# PR2387_FETs.net
KiCad netlist of a schematic drawn in Altium Designer
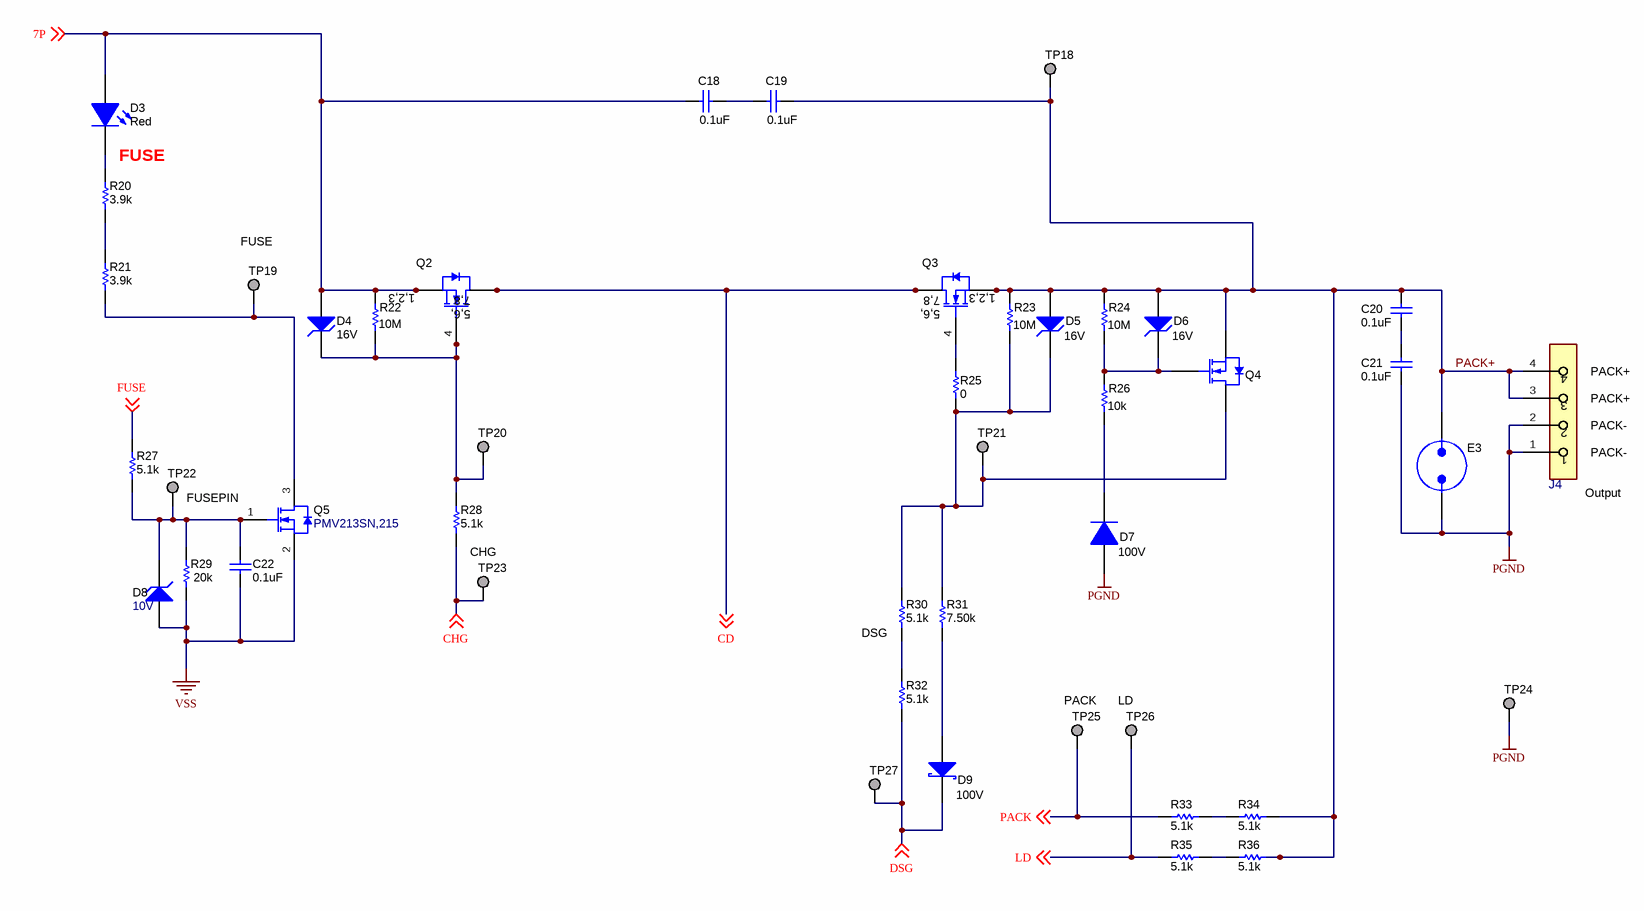
[diagram p0: PR2387_FETs.SchDoc]

(export (version "E")
  (design (tool "Eeschema 10.0.6"))
  (components
    (comp (ref "C18")
      (value "GCJ188R72A104KA01D")
      (footprint "0603")
      (description "CAP, CERM, 0.1 uF, 100 V,+/- 10%, X7R, AEC-Q200 Grade 1, 0603")
      (fields
        (field (name "MANUFACTURER") "MuRata")
        (field (name "VALUEDISPLAYED") "0.1uF")
        (field (name "PUBLISHER") "Texas Instruments")
      )
      (libsource (lib "Altium Vault - TI") (part "Capacitor"))
    )
    (comp (ref "C19")
      (value "GCJ188R72A104KA01D")
      (footprint "0603")
      (description "CAP, CERM, 0.1 uF, 100 V,+/- 10%, X7R, AEC-Q200 Grade 1, 0603")
      (fields
        (field (name "MANUFACTURER") "MuRata")
        (field (name "VALUEDISPLAYED") "0.1uF")
        (field (name "PUBLISHER") "Texas Instruments")
      )
      (libsource (lib "Altium Vault - TI") (part "Capacitor"))
    )
    (comp (ref "C20")
      (value "GCJ188R72A104KA01D")
      (footprint "0603")
      (description "CAP, CERM, 0.1 uF, 100 V,+/- 10%, X7R, AEC-Q200 Grade 1, 0603")
      (fields
        (field (name "MANUFACTURER") "MuRata")
        (field (name "VALUEDISPLAYED") "0.1uF")
        (field (name "PUBLISHER") "Texas Instruments")
      )
      (libsource (lib "Altium Vault - TI") (part "Capacitor"))
    )
    (comp (ref "C21")
      (value "GCJ188R72A104KA01D")
      (footprint "0603")
      (description "CAP, CERM, 0.1 uF, 100 V,+/- 10%, X7R, AEC-Q200 Grade 1, 0603")
      (fields
        (field (name "MANUFACTURER") "MuRata")
        (field (name "VALUEDISPLAYED") "0.1uF")
        (field (name "PUBLISHER") "Texas Instruments")
      )
      (libsource (lib "Altium Vault - TI") (part "Capacitor"))
    )
    (comp (ref "C22")
      (value "885012206095")
      (footprint "0603")
      (description "CAP, CERM, 0.1 uF, 50 V, +/- 10%, X7R, 0603")
      (fields
        (field (name "VALUEDISPLAYED") "0.1uF")
        (field (name "MANUFACTURER") "Wurth Elektronik")
        (field (name "PUBLISHER") "Texas Instruments")
      )
      (libsource (lib "Altium Vault - TI") (part "Capacitor"))
    )
    (comp (ref "D3")
      (value "Red")
      (footprint "WL-SMCW_RED")
      (description "LED, Red, SMD")
      (fields (field (name "MANUFACTURER") "Wurth Elektronik") (field (name "PARTNUMBER") "150060RS75000"))
      (libsource (lib "Altium Vault - TI") (part "CMP-0002947-3"))
    )
    (comp (ref "D4")
      (value "16V")
      (footprint "SOD-123")
      (description "Diode, Zener, 16 V, 500 mW, SOD-123")
      (fields (field (name "MANUFACTURER") "Diodes Inc.") (field (name "PARTNUMBER") "MMSZ5246B-7-F"))
      (libsource (lib "Altium Vault - TI") (part "Zener"))
    )
    (comp (ref "D5")
      (value "16V")
      (footprint "SOD-123")
      (description "Diode, Zener, 16 V, 500 mW, SOD-123")
      (fields (field (name "PARTNUMBER") "MMSZ5246B-7-F") (field (name "MANUFACTURER") "Diodes Inc."))
      (libsource (lib "Altium Vault - TI") (part "CMP-0005754-4"))
    )
    (comp (ref "D6")
      (value "16V")
      (footprint "SOD-123")
      (description "Diode, Zener, 16 V, 500 mW, SOD-123")
      (fields (field (name "PARTNUMBER") "MMSZ5246B-7-F") (field (name "MANUFACTURER") "Diodes Inc."))
      (libsource (lib "Altium Vault - TI") (part "CMP-0005754-4"))
    )
    (comp (ref "D7")
      (value "100V")
      (footprint "SOD-123")
      (description "Diode, Ultrafast, 100 V, 0.15 A, SOD-123")
      (fields (field (name "PARTNUMBER") "1N4148W-7-F") (field (name "MANUFACTURER") "Diodes Inc."))
      (libsource (lib "Altium Vault - TI") (part "CMP-0029001-2"))
    )
    (comp (ref "D8")
      (value "10V")
      (footprint "SOD-123")
      (description "Diode, Zener, 10 V, 500 mW, SOD-123")
      (fields (field (name "MANUFACTURER") "ON Semiconductor") (field (name "PARTNUMBER") "MMSZ4697T1G"))
      (libsource (lib "Altium Vault - TI") (part "Zener"))
    )
    (comp (ref "D9")
      (value "BAT46W-7-F")
      (footprint "SOD-123")
      (description "Diode, Schottky, 100 V, 0.15 A, SOD-123")
      (fields (field (name "MANUFACTURER") "Diodes Inc.") (field (name "VR_V") "100V"))
      (libsource (lib "Altium Vault - TI") (part "DIODE_SCHOTTKY"))
    )
    (comp (ref "E3")
      (value "Spark Gap")
      (footprint "SPARK_GAP2")
      (libsource (lib "Altium Vault - TI") (part "CMP-0079939-1"))
    )
    (comp (ref "J4")
      (value "OSTTE040161")
      (footprint "FP-OSTTE040161_HDR4-MFG")
      (description "TERM BLOCK 3.5MM VERT 4POS PCB")
      (fields (field (name "MANUFACTURER") "On Shore Technology"))
      (libsource (lib "Altium Vault - TI") (part "SYM-OSTTE040161"))
    )
    (comp (ref "Q2")
      (value "CSD19532Q5B")
      (footprint "DNK0008A")
      (description "MOSFET, N-CH, 100 V, 17 A, DNK0008A (VSON-CLIP-8)")
      (fields (field (name "MANUFACTURER") "Texas Instruments"))
      (libsource (lib "Altium Vault - TI") (part "MOSFET_N_D56789G4S123"))
    )
    (comp (ref "Q3")
      (value "CSD19532Q5B")
      (footprint "DNK0008A")
      (description "MOSFET, N-CH, 100 V, 17 A, DNK0008A (VSON-CLIP-8)")
      (fields (field (name "MANUFACTURER") "Texas Instruments"))
      (libsource (lib "Altium Vault - TI") (part "MOSFET_N_D56789G4S123"))
    )
    (comp (ref "Q4")
      (value "MOSFET_N_D3G1S2")
      (footprint "SOT-323")
      (description "MOSFET, N-CH, 60 V, 0.31 A, SOT-323")
      (fields
        (field (name "PARTNUMBER") "2N7002KW")
        (field (name "MANUFACTURER") "Fairchild Semiconductor")
        (field (name "PUBLISHER") "Texas Instruments")
      )
      (libsource (lib "Altium Vault - TI") (part "CMP-0000774-1"))
    )
    (comp (ref "Q5")
      (value "PMV213SN,215")
      (footprint "SOT-23")
      (description "MOSFET, N-CH, 100 V, 1.9 A, SOT-23")
      (fields (field (name "MANUFACTURER") "Nexperia"))
      (libsource (lib "Altium Vault - TI") (part "MOSFET_N_D3G1S2"))
    )
    (comp (ref "R20")
      (value "CRCW06033K90JNEA")
      (footprint "0603")
      (description "RES, 3.9 k, 5%, 0.1 W, AEC-Q200 Grade 0, 0603")
      (fields (field (name "MANUFACTURER") "Vishay-Dale") (field (name "VALUEDISPLAYED") "3.9k"))
      (libsource (lib "Altium Vault - TI") (part "Resistor"))
    )
    (comp (ref "R21")
      (value "CRCW06033K90JNEA")
      (footprint "0603")
      (description "RES, 3.9 k, 5%, 0.1 W, AEC-Q200 Grade 0, 0603")
      (fields (field (name "MANUFACTURER") "Vishay-Dale") (field (name "VALUEDISPLAYED") "3.9k"))
      (libsource (lib "Altium Vault - TI") (part "Resistor"))
    )
    (comp (ref "R22")
      (value "Resistor")
      (footprint "0603")
      (description "RES, 10 M, 5%, 0.1 W, AEC-Q200 Grade 0, 0603")
      (fields
        (field (name "PARTNUMBER") "CRCW060310M0JNEA")
        (field (name "MANUFACTURER") "Vishay-Dale")
        (field (name "VALUEDISPLAYED") "10M")
        (field (name "PUBLISHER") "Texas Instruments")
      )
      (libsource (lib "Altium Vault - TI") (part "Resistor"))
    )
    (comp (ref "R23")
      (value "Resistor")
      (footprint "0603")
      (description "RES, 10 M, 5%, 0.1 W, AEC-Q200 Grade 0, 0603")
      (fields
        (field (name "PARTNUMBER") "CRCW060310M0JNEA")
        (field (name "MANUFACTURER") "Vishay-Dale")
        (field (name "VALUEDISPLAYED") "10M")
        (field (name "PUBLISHER") "Texas Instruments")
      )
      (libsource (lib "Altium Vault - TI") (part "Resistor"))
    )
    (comp (ref "R24")
      (value "Resistor")
      (footprint "0603")
      (description "RES, 10 M, 5%, 0.1 W, AEC-Q200 Grade 0, 0603")
      (fields
        (field (name "PARTNUMBER") "CRCW060310M0JNEA")
        (field (name "MANUFACTURER") "Vishay-Dale")
        (field (name "VALUEDISPLAYED") "10M")
        (field (name "PUBLISHER") "Texas Instruments")
      )
      (libsource (lib "Altium Vault - TI") (part "Resistor"))
    )
    (comp (ref "R25")
      (value "CRCW06030000Z0EA")
      (footprint "0603")
      (description "RES, 0, 5%, 0.1 W, AEC-Q200 Grade 0, 0603")
      (fields (field (name "MANUFACTURER") "Vishay-Dale") (field (name "VALUEDISPLAYED") "0"))
      (libsource (lib "Altium Vault - TI") (part "Resistor"))
    )
    (comp (ref "R26")
      (value "Resistor")
      (footprint "0603")
      (description "RES, 10 k, 5%, 0.1 W, AEC-Q200 Grade 0, 0603")
      (fields
        (field (name "PARTNUMBER") "CRCW060310K0JNEA")
        (field (name "MANUFACTURER") "Vishay-Dale")
        (field (name "VALUEDISPLAYED") "10k")
        (field (name "PUBLISHER") "Texas Instruments")
      )
      (libsource (lib "Altium Vault - TI") (part "Resistor"))
    )
    (comp (ref "R27")
      (value "Resistor")
      (footprint "0603")
      (description "RES, 5.1 k, 5%, 0.1 W, AEC-Q200 Grade 0, 0603")
      (fields
        (field (name "PARTNUMBER") "CRCW06035K10JNEA")
        (field (name "MANUFACTURER") "Vishay-Dale")
        (field (name "VALUEDISPLAYED") "5.1k")
        (field (name "PUBLISHER") "Texas Instruments")
      )
      (libsource (lib "Altium Vault - TI") (part "Resistor"))
    )
    (comp (ref "R28")
      (value "CRCW06035K10JNEA")
      (footprint "0603")
      (description "RES, 5.1 k, 5%, 0.1 W, AEC-Q200 Grade 0, 0603")
      (fields (field (name "VALUEDISPLAYED") "5.1k") (field (name "MANUFACTURER") "Vishay-Dale"))
      (libsource (lib "Altium Vault - TI") (part "Resistor"))
    )
    (comp (ref "R29")
      (value "Resistor")
      (footprint "0603")
      (description "RES, 20 k, 5%, 0.1 W, AEC-Q200 Grade 0, 0603")
      (fields
        (field (name "PARTNUMBER") "CRCW060320K0JNEA")
        (field (name "MANUFACTURER") "Vishay-Dale")
        (field (name "VALUEDISPLAYED") "20k")
        (field (name "PUBLISHER") "Texas Instruments")
      )
      (libsource (lib "Altium Vault - TI") (part "Resistor"))
    )
    (comp (ref "R30")
      (value "CRCW12065K10JNEA")
      (footprint "1206")
      (description "RES, 5.1 k, 5%, 0.25 W, AEC-Q200 Grade 0, 1206")
      (fields (field (name "VALUEDISPLAYED") "5.1k") (field (name "MANUFACTURER") "Vishay-Dale"))
      (libsource (lib "Altium Vault - TI") (part "Resistor"))
    )
    (comp (ref "R31")
      (value "CRCW06037K50FKEA")
      (footprint "0603")
      (description "RES, 7.50 k, 1%, 0.1 W, AEC-Q200 Grade 0, 0603")
      (fields (field (name "MANUFACTURER") "Vishay-Dale") (field (name "VALUEDISPLAYED") "7.50k"))
      (libsource (lib "Altium Vault - TI") (part "Resistor"))
    )
    (comp (ref "R32")
      (value "CRCW12065K10JNEA")
      (footprint "1206")
      (description "RES, 5.1 k, 5%, 0.25 W, AEC-Q200 Grade 0, 1206")
      (fields (field (name "VALUEDISPLAYED") "5.1k") (field (name "MANUFACTURER") "Vishay-Dale"))
      (libsource (lib "Altium Vault - TI") (part "Resistor"))
    )
    (comp (ref "R33")
      (value "CRCW12065K10JNEA")
      (footprint "1206")
      (description "RES, 5.1 k, 5%, 0.25 W, AEC-Q200 Grade 0, 1206")
      (fields (field (name "VALUEDISPLAYED") "5.1k") (field (name "MANUFACTURER") "Vishay-Dale"))
      (libsource (lib "Altium Vault - TI") (part "Resistor"))
    )
    (comp (ref "R34")
      (value "CRCW12065K10JNEA")
      (footprint "1206")
      (description "RES, 5.1 k, 5%, 0.25 W, AEC-Q200 Grade 0, 1206")
      (fields (field (name "VALUEDISPLAYED") "5.1k") (field (name "MANUFACTURER") "Vishay-Dale"))
      (libsource (lib "Altium Vault - TI") (part "Resistor"))
    )
    (comp (ref "R35")
      (value "CRCW12065K10JNEA")
      (footprint "1206")
      (description "RES, 5.1 k, 5%, 0.25 W, AEC-Q200 Grade 0, 1206")
      (fields (field (name "VALUEDISPLAYED") "5.1k") (field (name "MANUFACTURER") "Vishay-Dale"))
      (libsource (lib "Altium Vault - TI") (part "Resistor"))
    )
    (comp (ref "R36")
      (value "CRCW12065K10JNEA")
      (footprint "1206")
      (description "RES, 5.1 k, 5%, 0.25 W, AEC-Q200 Grade 0, 1206")
      (fields (field (name "VALUEDISPLAYED") "5.1k") (field (name "MANUFACTURER") "Vishay-Dale"))
      (libsource (lib "Altium Vault - TI") (part "Resistor"))
    )
    (comp (ref "TP18")
      (value "TESTPOINT")
      (footprint "TP_VIA_060RND040")
      (description "TEST POINT.  No entry in BOM.")
      (libsource (lib "Altium Vault - TI") (part "TESTPOINT"))
    )
    (comp (ref "TP19")
      (value "TESTPOINT")
      (footprint "TP_VIA_060RND040")
      (description "TEST POINT.  No entry in BOM.")
      (libsource (lib "Altium Vault - TI") (part "TESTPOINT"))
    )
    (comp (ref "TP20")
      (value "TESTPOINT")
      (footprint "TP_VIA_060RND040")
      (description "TEST POINT.  No entry in BOM.")
      (libsource (lib "Altium Vault - TI") (part "TESTPOINT"))
    )
    (comp (ref "TP21")
      (value "TESTPOINT")
      (footprint "TP_VIA_060RND040")
      (description "TEST POINT.  No entry in BOM.")
      (libsource (lib "Altium Vault - TI") (part "TESTPOINT"))
    )
    (comp (ref "TP22")
      (value "TESTPOINT")
      (footprint "TP_VIA_060RND040")
      (description "TEST POINT.  No entry in BOM.")
      (libsource (lib "Altium Vault - TI") (part "TESTPOINT"))
    )
    (comp (ref "TP23")
      (value "TESTPOINT")
      (footprint "TP_VIA_060RND040")
      (description "TEST POINT.  No entry in BOM.")
      (libsource (lib "Altium Vault - TI") (part "TESTPOINT"))
    )
    (comp (ref "TP24")
      (value "TESTPOINT")
      (footprint "TP_VIA_060RND040")
      (description "TEST POINT.  No entry in BOM.")
      (libsource (lib "Altium Vault - TI") (part "TESTPOINT"))
    )
    (comp (ref "TP25")
      (value "TESTPOINT")
      (footprint "TP_VIA_060RND040")
      (description "TEST POINT.  No entry in BOM.")
      (libsource (lib "Altium Vault - TI") (part "TESTPOINT"))
    )
    (comp (ref "TP26")
      (value "TESTPOINT")
      (footprint "TP_VIA_060RND040")
      (description "TEST POINT.  No entry in BOM.")
      (libsource (lib "Altium Vault - TI") (part "TESTPOINT"))
    )
    (comp (ref "TP27")
      (value "TESTPOINT")
      (footprint "TP_VIA_060RND040")
      (description "TEST POINT.  No entry in BOM.")
      (libsource (lib "Altium Vault - TI") (part "TESTPOINT"))
    )
  )
  (nets
    (net (code "1") (name "/PACK+") (class "Default")
      (node (ref "C19") (pin "1") (pinfunction "1_1") (pintype "passive"))
      (node (ref "C20") (pin "1") (pinfunction "1_1") (pintype "passive"))
      (node (ref "D5") (pin "2") (pinfunction "A_2") (pintype "passive"))
      (node (ref "D6") (pin "2") (pinfunction "A_2") (pintype "passive"))
      (node (ref "E3") (pin "1") (pinfunction "1_1") (pintype "passive"))
      (node (ref "J4") (pin "3") (pinfunction "3_3") (pintype "passive"))
      (node (ref "J4") (pin "4") (pinfunction "4_4") (pintype "passive"))
      (node (ref "Q3") (pin "1") (pinfunction "S_1") (pintype "passive"))
      (node (ref "Q3") (pin "2") (pinfunction "S_2") (pintype "passive"))
      (node (ref "Q3") (pin "3") (pinfunction "S_3") (pintype "passive"))
      (node (ref "Q4") (pin "2") (pinfunction "S_2") (pintype "passive"))
      (node (ref "R23") (pin "1") (pinfunction "1_1") (pintype "passive"))
      (node (ref "R24") (pin "1") (pinfunction "1_1") (pintype "passive"))
      (node (ref "R34") (pin "1") (pinfunction "1_1") (pintype "passive"))
      (node (ref "R36") (pin "1") (pinfunction "1_1") (pintype "passive"))
      (node (ref "TP18") (pin "1") (pintype "passive"))
    )
    (net (code "2") (name "7P") (class "Default")
      (node (ref "C18") (pin "2") (pinfunction "2_2") (pintype "passive"))
      (node (ref "D3") (pin "2") (pinfunction "A_2") (pintype "passive"))
      (node (ref "D4") (pin "2") (pinfunction "A_2") (pintype "passive"))
      (node (ref "Q2") (pin "1") (pinfunction "S_1") (pintype "passive"))
      (node (ref "Q2") (pin "2") (pinfunction "S_2") (pintype "passive"))
      (node (ref "Q2") (pin "3") (pinfunction "S_3") (pintype "passive"))
      (node (ref "R22") (pin "1") (pinfunction "1_1") (pintype "passive"))
    )
    (net (code "3") (name "CD") (class "Default")
      (node (ref "Q2") (pin "5") (pinfunction "D_5") (pintype "passive"))
      (node (ref "Q2") (pin "6") (pinfunction "D_6") (pintype "passive"))
      (node (ref "Q2") (pin "7") (pinfunction "D_7") (pintype "passive"))
      (node (ref "Q2") (pin "8") (pinfunction "D_8") (pintype "passive"))
      (node (ref "Q2") (pin "9") (pinfunction "D_9") (pintype "passive"))
      (node (ref "Q3") (pin "5") (pinfunction "D_5") (pintype "passive"))
      (node (ref "Q3") (pin "6") (pinfunction "D_6") (pintype "passive"))
      (node (ref "Q3") (pin "7") (pinfunction "D_7") (pintype "passive"))
      (node (ref "Q3") (pin "8") (pinfunction "D_8") (pintype "passive"))
      (node (ref "Q3") (pin "9") (pinfunction "D_9") (pintype "passive"))
    )
    (net (code "4") (name "CHG") (class "Default")
      (node (ref "R28") (pin "1") (pinfunction "1_1") (pintype "passive"))
      (node (ref "TP23") (pin "1") (pintype "passive"))
    )
    (net (code "5") (name "DSG") (class "Default")
      (node (ref "D9") (pin "1") (pinfunction "K_1") (pintype "passive"))
      (node (ref "R32") (pin "1") (pinfunction "1_1") (pintype "passive"))
      (node (ref "TP27") (pin "1") (pintype "passive"))
    )
    (net (code "6") (name "FUSE") (class "Default")
      (node (ref "R27") (pin "2") (pinfunction "2_2") (pintype "passive"))
    )
    (net (code "7") (name "LD") (class "Default")
      (node (ref "R35") (pin "2") (pinfunction "2_2") (pintype "passive"))
      (node (ref "TP26") (pin "1") (pintype "passive"))
    )
    (net (code "8") (name "Net-(C18-Pad1)") (class "Default")
      (node (ref "C18") (pin "1") (pinfunction "1_1") (pintype "passive"))
      (node (ref "C19") (pin "2") (pinfunction "2_2") (pintype "passive"))
    )
    (net (code "9") (name "Net-(C20-Pad2)") (class "Default")
      (node (ref "C20") (pin "2") (pinfunction "2_2") (pintype "passive"))
      (node (ref "C21") (pin "1") (pinfunction "1_1") (pintype "passive"))
    )
    (net (code "10") (name "Net-(D3-K)") (class "Default")
      (node (ref "D3") (pin "1") (pinfunction "K_1") (pintype "passive"))
      (node (ref "R20") (pin "2") (pinfunction "2_2") (pintype "passive"))
    )
    (net (code "11") (name "Net-(D4-K)") (class "Default")
      (node (ref "D4") (pin "1") (pinfunction "K_1") (pintype "passive"))
      (node (ref "Q2") (pin "4") (pinfunction "G_4") (pintype "passive"))
      (node (ref "R22") (pin "2") (pinfunction "2_2") (pintype "passive"))
      (node (ref "R28") (pin "2") (pinfunction "2_2") (pintype "passive"))
      (node (ref "TP20") (pin "1") (pintype "passive"))
    )
    (net (code "12") (name "Net-(D5-K)") (class "Default")
      (node (ref "D5") (pin "1") (pinfunction "K_1") (pintype "passive"))
      (node (ref "Q4") (pin "3") (pinfunction "D_3") (pintype "passive"))
      (node (ref "R23") (pin "2") (pinfunction "2_2") (pintype "passive"))
      (node (ref "R25") (pin "2") (pinfunction "2_2") (pintype "passive"))
      (node (ref "R30") (pin "2") (pinfunction "2_2") (pintype "passive"))
      (node (ref "R31") (pin "2") (pinfunction "2_2") (pintype "passive"))
      (node (ref "TP21") (pin "1") (pintype "passive"))
    )
    (net (code "13") (name "Net-(D6-K)") (class "Default")
      (node (ref "D6") (pin "1") (pinfunction "K_1") (pintype "passive"))
      (node (ref "Q4") (pin "1") (pinfunction "G_1") (pintype "passive"))
      (node (ref "R24") (pin "2") (pinfunction "2_2") (pintype "passive"))
      (node (ref "R26") (pin "1") (pinfunction "1_1") (pintype "passive"))
    )
    (net (code "14") (name "Net-(D7-K)") (class "Default")
      (node (ref "D7") (pin "1") (pinfunction "K_1") (pintype "passive"))
      (node (ref "R26") (pin "2") (pinfunction "2_2") (pintype "passive"))
    )
    (net (code "15") (name "Net-(D8-K)") (class "Default")
      (node (ref "C22") (pin "2") (pinfunction "2_2") (pintype "passive"))
      (node (ref "D8") (pin "1") (pinfunction "K_1") (pintype "passive"))
      (node (ref "Q5") (pin "1") (pinfunction "G_1") (pintype "passive"))
      (node (ref "R27") (pin "1") (pinfunction "1_1") (pintype "passive"))
      (node (ref "R29") (pin "2") (pinfunction "2_2") (pintype "passive"))
      (node (ref "TP22") (pin "1") (pintype "passive"))
    )
    (net (code "16") (name "Net-(D9-A)") (class "Default")
      (node (ref "D9") (pin "2") (pinfunction "A_2") (pintype "passive"))
      (node (ref "R31") (pin "1") (pinfunction "1_1") (pintype "passive"))
    )
    (net (code "17") (name "Net-(Q3-G)") (class "Default")
      (node (ref "Q3") (pin "4") (pinfunction "G_4") (pintype "passive"))
      (node (ref "R25") (pin "1") (pinfunction "1_1") (pintype "passive"))
    )
    (net (code "18") (name "Net-(Q5-D)") (class "Default")
      (node (ref "Q5") (pin "3") (pinfunction "D_3") (pintype "passive"))
      (node (ref "R21") (pin "1") (pinfunction "1_1") (pintype "passive"))
      (node (ref "TP19") (pin "1") (pintype "passive"))
    )
    (net (code "19") (name "Net-(R20-Pad1)") (class "Default")
      (node (ref "R20") (pin "1") (pinfunction "1_1") (pintype "passive"))
      (node (ref "R21") (pin "2") (pinfunction "2_2") (pintype "passive"))
    )
    (net (code "20") (name "Net-(R30-Pad1)") (class "Default")
      (node (ref "R30") (pin "1") (pinfunction "1_1") (pintype "passive"))
      (node (ref "R32") (pin "2") (pinfunction "2_2") (pintype "passive"))
    )
    (net (code "21") (name "Net-(R33-Pad1)") (class "Default")
      (node (ref "R33") (pin "1") (pinfunction "1_1") (pintype "passive"))
      (node (ref "R34") (pin "2") (pinfunction "2_2") (pintype "passive"))
    )
    (net (code "22") (name "Net-(R35-Pad1)") (class "Default")
      (node (ref "R35") (pin "1") (pinfunction "1_1") (pintype "passive"))
      (node (ref "R36") (pin "2") (pinfunction "2_2") (pintype "passive"))
    )
    (net (code "23") (name "PACK") (class "Default")
      (node (ref "R33") (pin "2") (pinfunction "2_2") (pintype "passive"))
      (node (ref "TP25") (pin "1") (pintype "passive"))
    )
    (net (code "24") (name "PGND") (class "Default")
      (node (ref "C21") (pin "2") (pinfunction "2_2") (pintype "passive"))
      (node (ref "D7") (pin "2") (pinfunction "A_2") (pintype "passive"))
      (node (ref "E3") (pin "2") (pinfunction "2_2") (pintype "passive"))
      (node (ref "J4") (pin "1") (pinfunction "1_1") (pintype "passive"))
      (node (ref "J4") (pin "2") (pinfunction "2_2") (pintype "passive"))
      (node (ref "TP24") (pin "1") (pintype "passive"))
    )
    (net (code "25") (name "VSS") (class "Default")
      (node (ref "C22") (pin "1") (pinfunction "1_1") (pintype "passive"))
      (node (ref "D8") (pin "2") (pinfunction "A_2") (pintype "passive"))
      (node (ref "Q5") (pin "2") (pinfunction "S_2") (pintype "passive"))
      (node (ref "R29") (pin "1") (pinfunction "1_1") (pintype "passive"))
    )
  )
)
